# i3_Button-v03_4_4.net
KiCad netlist of a schematic drawn in EAGLE
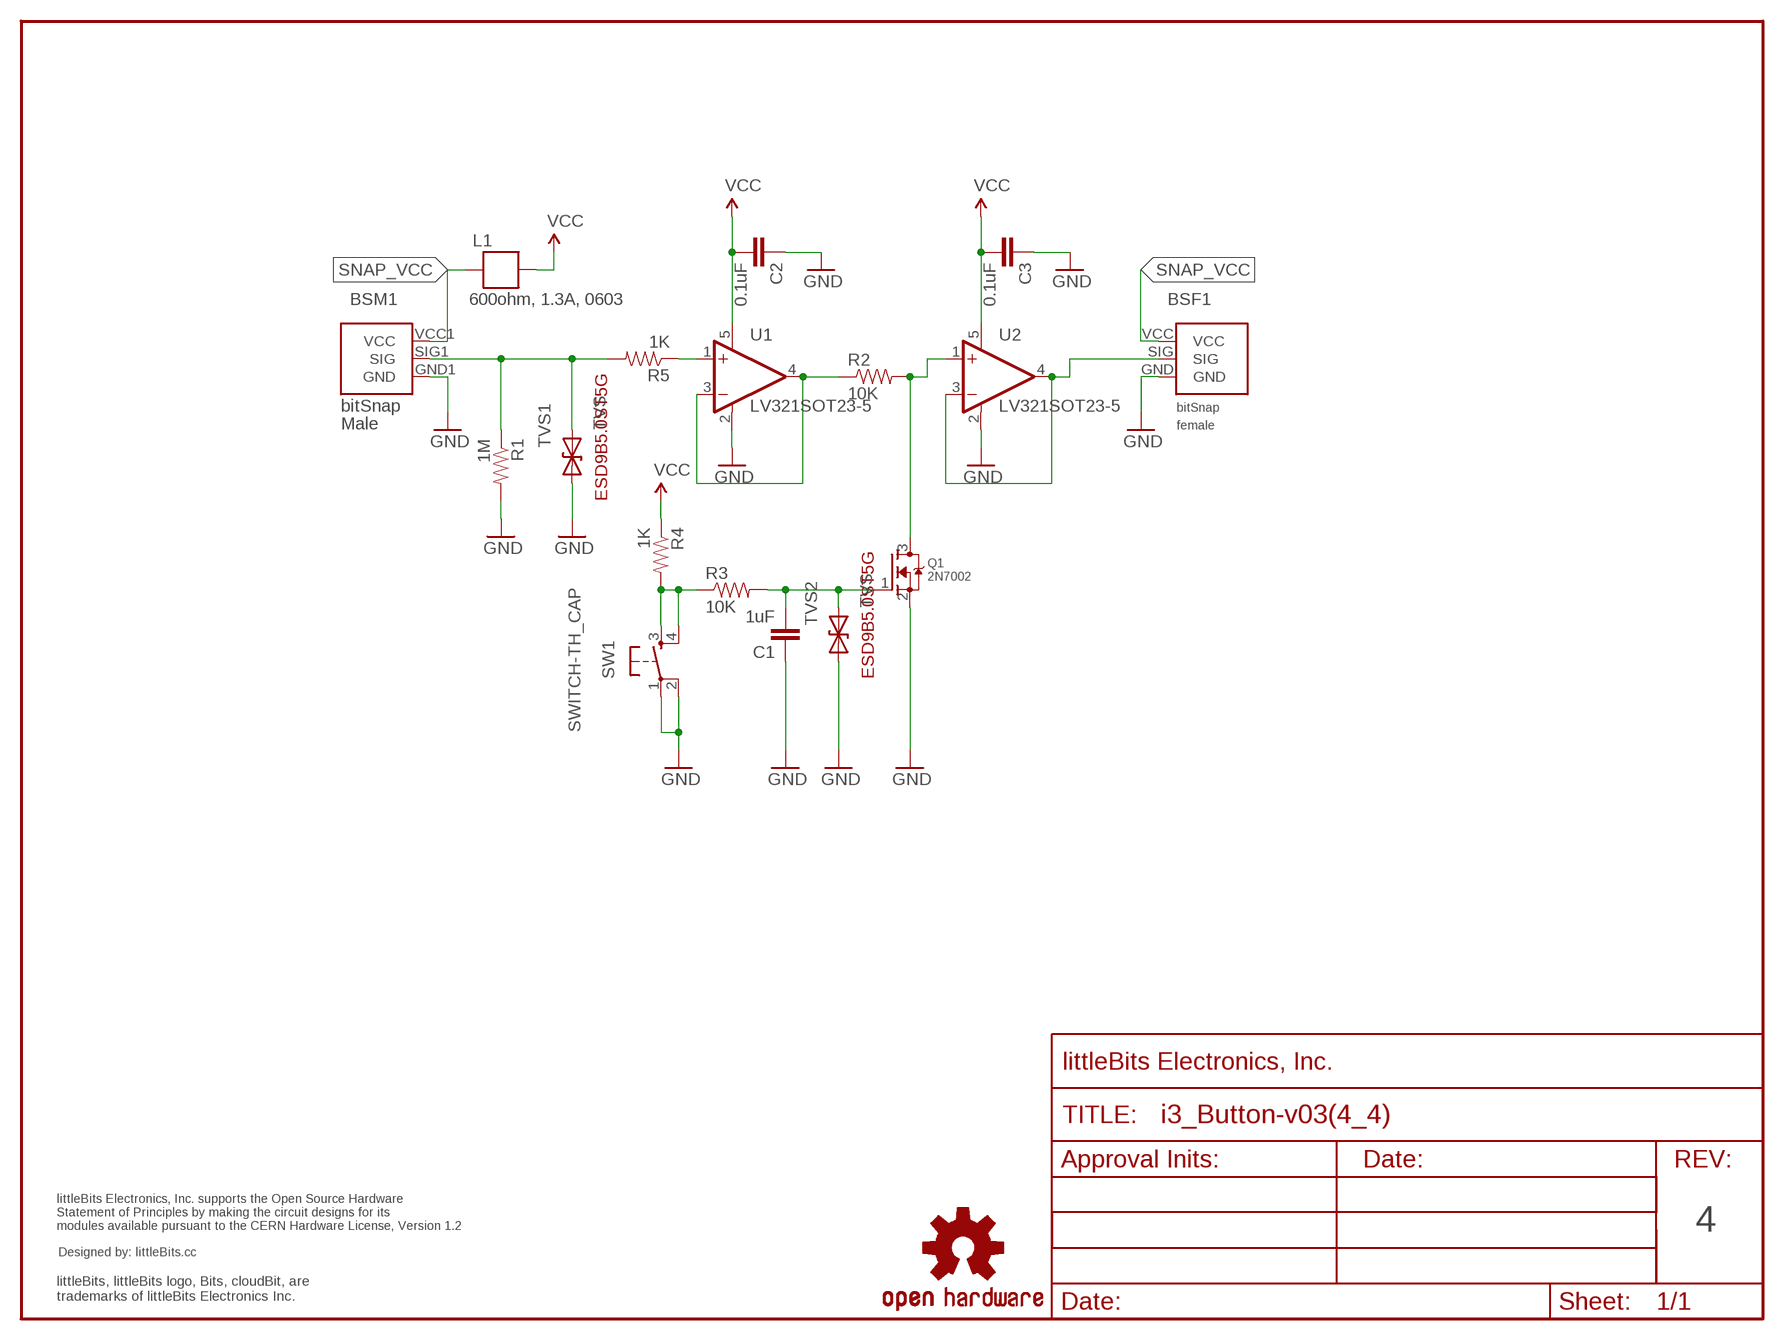
[diagram p0: schematic, sheet 1]

(export (version "E")
  (design (tool "Eeschema 10.0.6"))
  (components
    (comp (ref "BSF1")
      (value "BITSNAP_V03_FEMALE")
      (footprint "eagle-import:BITSNAP_V03_FEMALE")
      (libsource (lib "eagle-import") (part "BITSNAP_V03_FEMALE"))
    )
    (comp (ref "BSM1")
      (value "BITSNAP_V03_MALE")
      (footprint "eagle-import:BITSNAP_V03_MALE")
      (libsource (lib "eagle-import") (part "BITSNAP_V03_MALE"))
    )
    (comp (ref "C1")
      (value "1uF")
      (footprint "eagle-import:0603-CAP")
      (libsource (lib "eagle-import") (part "CAP0603-CAP"))
    )
    (comp (ref "C2")
      (value "0.1uF")
      (footprint "eagle-import:0603-CAP")
      (libsource (lib "eagle-import") (part "CAP0603-CAP"))
    )
    (comp (ref "C3")
      (value "0.1uF")
      (footprint "eagle-import:0603-CAP")
      (libsource (lib "eagle-import") (part "CAP0603-CAP"))
    )
    (comp (ref "FRAME1")
      (value "FRAME-LETTER-OHWOHW")
      (footprint "eagle-import:FABDWG01-OHW")
      (libsource (lib "eagle-import") (part "FRAME-LETTER-OHWOHW"))
    )
    (comp (ref "L1")
      (value "600ohm, 1.3A, 0603")
      (footprint "eagle-import:R0603")
      (libsource (lib "eagle-import") (part "FERRITE-BEAD"))
    )
    (comp (ref "Q1")
      (value "2N7002")
      (footprint "eagle-import:SOT23")
      (libsource (lib "eagle-import") (part "MOSFET-NREFLOW"))
    )
    (comp (ref "R1")
      (value "1M")
      (footprint "eagle-import:0603-RES")
      (libsource (lib "eagle-import") (part "RESISTOR0603-RES"))
    )
    (comp (ref "R2")
      (value "10K")
      (footprint "eagle-import:0603-RES")
      (libsource (lib "eagle-import") (part "RESISTOR0603-RES"))
    )
    (comp (ref "R3")
      (value "10K")
      (footprint "eagle-import:0603-RES")
      (libsource (lib "eagle-import") (part "RESISTOR0603-RES"))
    )
    (comp (ref "R4")
      (value "1K")
      (footprint "eagle-import:0603-RES")
      (libsource (lib "eagle-import") (part "RESISTOR0603-RES"))
    )
    (comp (ref "R5")
      (value "1K")
      (footprint "eagle-import:0603-RES")
      (libsource (lib "eagle-import") (part "RESISTOR0603-RES"))
    )
    (comp (ref "SW1")
      (value "SWITCH-TH_CAP")
      (footprint "eagle-import:SWITCH-TH_CAP")
      (libsource (lib "eagle-import") (part "SWITCH-TH_CAP"))
    )
    (comp (ref "TVS1")
      (value "TVS")
      (footprint "eagle-import:SOD-923")
      (fields (field (name "MPN") "ESD9B5.0ST5G"))
      (libsource (lib "eagle-import") (part "DIODE-TVSSOD-923"))
    )
    (comp (ref "TVS2")
      (value "TVS")
      (footprint "eagle-import:SOD-923")
      (fields (field (name "MPN") "ESD9B5.0ST5G"))
      (libsource (lib "eagle-import") (part "DIODE-TVSSOD-923"))
    )
    (comp (ref "U$1")
      (value "OSHW-LOGOL")
      (footprint "eagle-import:OSHW-LOGO-L")
      (libsource (lib "eagle-import") (part "OSHW-LOGOL"))
    )
    (comp (ref "U$2")
      (value "OSHWCREDIT")
      (footprint "eagle-import:OSHWCREDIT")
      (libsource (lib "eagle-import") (part "OSHWCREDIT"))
    )
    (comp (ref "U1")
      (value "LV321SOT23-5")
      (footprint "eagle-import:SOT23-5")
      (libsource (lib "eagle-import") (part "LV321SOT23-5"))
    )
    (comp (ref "U2")
      (value "LV321SOT23-5")
      (footprint "eagle-import:SOT23-5")
      (libsource (lib "eagle-import") (part "LV321SOT23-5"))
    )
  )
  (nets
    (net (code "1") (name "GND") (class "Default")
      (node (ref "BSF1") (pin "GND") (pinfunction "GND_GND") (pintype "bidirectional"))
      (node (ref "BSM1") (pin "GND1") (pinfunction "GND_GND1") (pintype "bidirectional"))
      (node (ref "C1") (pin "1") (pinfunction "1_1") (pintype "passive"))
      (node (ref "C2") (pin "1") (pinfunction "1_1") (pintype "passive"))
      (node (ref "C3") (pin "1") (pinfunction "1_1") (pintype "passive"))
      (node (ref "Q1") (pin "2") (pinfunction "S_2") (pintype "bidirectional"))
      (node (ref "R1") (pin "2") (pinfunction "2_2") (pintype "passive"))
      (node (ref "SW1") (pin "1") (pinfunction "1_1") (pintype "passive"))
      (node (ref "SW1") (pin "2") (pinfunction "2_2") (pintype "passive"))
      (node (ref "TVS1") (pin "1") (pinfunction "A_1") (pintype "passive"))
      (node (ref "TVS2") (pin "1") (pinfunction "A_1") (pintype "passive"))
      (node (ref "U1") (pin "2") (pinfunction "V-_2") (pintype "power_in"))
      (node (ref "U2") (pin "2") (pinfunction "V-_2") (pintype "power_in"))
    )
    (net (code "2") (name "Net-(BSM1-SIG)") (class "Default")
      (node (ref "BSM1") (pin "SIG1") (pinfunction "SIG_SIG1") (pintype "bidirectional"))
      (node (ref "R1") (pin "1") (pinfunction "1_1") (pintype "passive"))
      (node (ref "R5") (pin "2") (pinfunction "2_2") (pintype "passive"))
      (node (ref "TVS1") (pin "2") (pinfunction "C_2") (pintype "passive"))
    )
    (net (code "3") (name "Net-(Q1-D)") (class "Default")
      (node (ref "Q1") (pin "3") (pinfunction "D_3") (pintype "bidirectional"))
      (node (ref "R2") (pin "2") (pinfunction "2_2") (pintype "passive"))
      (node (ref "U2") (pin "1") (pinfunction "+IN_1") (pintype "input"))
    )
    (net (code "4") (name "Net-(Q1-G)") (class "Default")
      (node (ref "C1") (pin "2") (pinfunction "2_2") (pintype "passive"))
      (node (ref "Q1") (pin "1") (pinfunction "G_1") (pintype "bidirectional"))
      (node (ref "R3") (pin "2") (pinfunction "2_2") (pintype "passive"))
      (node (ref "TVS2") (pin "2") (pinfunction "C_2") (pintype "passive"))
    )
    (net (code "5") (name "Net-(R3-Pad1)") (class "Default")
      (node (ref "R3") (pin "1") (pinfunction "1_1") (pintype "passive"))
      (node (ref "R4") (pin "2") (pinfunction "2_2") (pintype "passive"))
      (node (ref "SW1") (pin "3") (pinfunction "3_3") (pintype "passive"))
      (node (ref "SW1") (pin "4") (pinfunction "4_4") (pintype "passive"))
    )
    (net (code "6") (name "Net-(U1-+IN)") (class "Default")
      (node (ref "R5") (pin "1") (pinfunction "1_1") (pintype "passive"))
      (node (ref "U1") (pin "1") (pinfunction "+IN_1") (pintype "input"))
    )
    (net (code "7") (name "Net-(U1--IN)") (class "Default")
      (node (ref "R2") (pin "1") (pinfunction "1_1") (pintype "passive"))
      (node (ref "U1") (pin "3") (pinfunction "-IN_3") (pintype "input"))
      (node (ref "U1") (pin "4") (pinfunction "OUT_4") (pintype "output"))
    )
    (net (code "8") (name "Net-(U2--IN)") (class "Default")
      (node (ref "BSF1") (pin "SIG") (pinfunction "SIG_SIG") (pintype "bidirectional"))
      (node (ref "U2") (pin "3") (pinfunction "-IN_3") (pintype "input"))
      (node (ref "U2") (pin "4") (pinfunction "OUT_4") (pintype "output"))
    )
    (net (code "9") (name "SNAP_VCC") (class "Default")
      (node (ref "BSF1") (pin "VCC") (pinfunction "VCC_VCC") (pintype "bidirectional"))
      (node (ref "BSM1") (pin "VCC1") (pinfunction "VCC_VCC1") (pintype "bidirectional"))
      (node (ref "L1") (pin "2") (pinfunction "P$2_2") (pintype "bidirectional"))
    )
    (net (code "10") (name "VCC") (class "Default")
      (node (ref "C2") (pin "2") (pinfunction "2_2") (pintype "passive"))
      (node (ref "C3") (pin "2") (pinfunction "2_2") (pintype "passive"))
      (node (ref "L1") (pin "1") (pinfunction "P$1_1") (pintype "bidirectional"))
      (node (ref "R4") (pin "1") (pinfunction "1_1") (pintype "passive"))
      (node (ref "U1") (pin "5") (pinfunction "V+_5") (pintype "power_in"))
      (node (ref "U2") (pin "5") (pinfunction "V+_5") (pintype "power_in"))
    )
  )
)
